# Arduino.net
KiCad netlist of a schematic drawn in Altium Designer
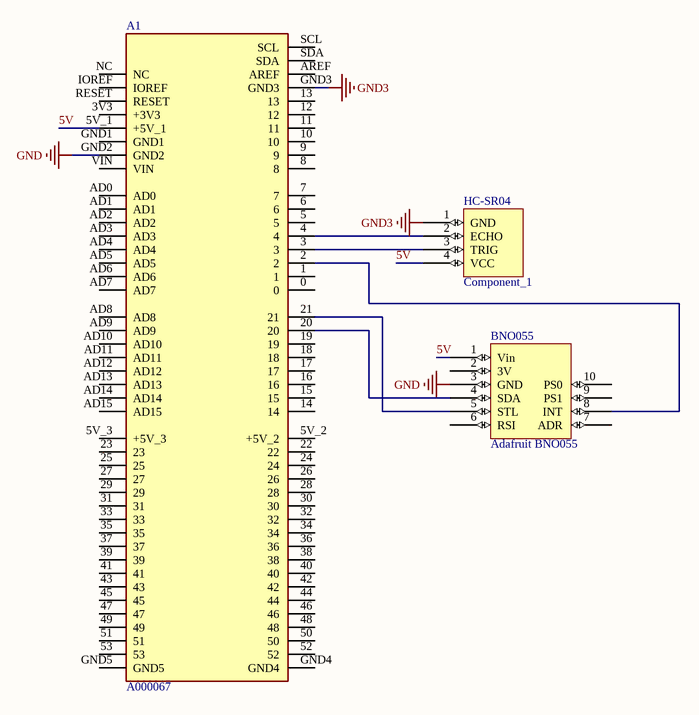
[diagram p0: Arduino.SchDoc]

(export (version "E")
  (design (tool "Eeschema 10.0.6"))
  (components
    (comp (ref "A1")
      (value "A000067")
      (footprint "ARDUINO_A000067")
      (description "8-bit board with 54 digital pins, 16 analog inputs, and 4 serial ports.")
      (fields (field (name "MF") "Arduino") (field (name "MP") "Arduino Mega 2560 Rev3"))
      (libsource (lib "A000067") (part "A000067"))
    )
    (comp (ref "BNO055")
      (value "Adafruit BNO055")
      (footprint "PCBComponent_1")
      (libsource (lib "Adafruit BNO055") (part "Component_1"))
    )
    (comp (ref "HC-SR04")
      (value "Component_1")
      (footprint "Ultrasonic Header:PCBComponent_1")
      (libsource (lib "Ultrasonic Header") (part "Component_1"))
    )
  )
  (nets
    (net (code "1") (name "/5V") (class "Default")
      (node (ref "A1") (pin "5V_1") (pinfunction "+5V_1_5V_1") (pintype "passive"))
      (node (ref "BNO055") (pin "1") (pinfunction "Vin_1") (pintype "bidirectional"))
      (node (ref "HC-SR04") (pin "4") (pinfunction "VCC_4") (pintype "bidirectional"))
    )
    (net (code "2") (name "GND") (class "Default")
      (node (ref "A1") (pin "GND2") (pinfunction "GND2_GND2") (pintype "passive"))
      (node (ref "BNO055") (pin "3") (pinfunction "GND_3") (pintype "bidirectional"))
    )
    (net (code "3") (name "GND3") (class "Default")
      (node (ref "A1") (pin "GND3") (pinfunction "GND3_GND3") (pintype "passive"))
      (node (ref "HC-SR04") (pin "1") (pinfunction "GND_1") (pintype "bidirectional"))
    )
    (net (code "4") (name "Net-(BNO055-INT)") (class "Default")
      (node (ref "A1") (pin "2") (pinfunction "2_2") (pintype "passive"))
      (node (ref "BNO055") (pin "8") (pinfunction "INT_8") (pintype "bidirectional"))
    )
    (net (code "5") (name "Net-(BNO055-SDA)") (class "Default")
      (node (ref "A1") (pin "20") (pinfunction "20_20") (pintype "passive"))
      (node (ref "BNO055") (pin "4") (pinfunction "SDA_4") (pintype "bidirectional"))
    )
    (net (code "6") (name "Net-(BNO055-STL)") (class "Default")
      (node (ref "A1") (pin "21") (pinfunction "21_21") (pintype "passive"))
      (node (ref "BNO055") (pin "5") (pinfunction "STL_5") (pintype "bidirectional"))
    )
    (net (code "7") (name "Net-(HC-SR04-ECHO)") (class "Default")
      (node (ref "A1") (pin "4") (pinfunction "4_4") (pintype "passive"))
      (node (ref "HC-SR04") (pin "2") (pinfunction "ECHO_2") (pintype "bidirectional"))
    )
    (net (code "8") (name "Net-(HC-SR04-TRIG)") (class "Default")
      (node (ref "A1") (pin "3") (pinfunction "3_3") (pintype "passive"))
      (node (ref "HC-SR04") (pin "3") (pinfunction "TRIG_3") (pintype "bidirectional"))
    )
    (net (code "9") (name "unconnected-(A1-+3V3-Pad3V3)") (class "Default")
      (node (ref "A1") (pin "3V3") (pinfunction "+3V3_3V3") (pintype "passive"))
    )
    (net (code "10") (name "unconnected-(A1-+5V_2-Pad5V_2)") (class "Default")
      (node (ref "A1") (pin "5V_2") (pinfunction "+5V_2_5V_2") (pintype "passive"))
    )
    (net (code "11") (name "unconnected-(A1-+5V_3-Pad5V_3)") (class "Default")
      (node (ref "A1") (pin "5V_3") (pinfunction "+5V_3_5V_3") (pintype "passive"))
    )
    (net (code "12") (name "unconnected-(A1-Pad0)") (class "Default")
      (node (ref "A1") (pin "0") (pinfunction "0_0") (pintype "passive"))
    )
    (net (code "13") (name "unconnected-(A1-Pad1)") (class "Default")
      (node (ref "A1") (pin "1") (pinfunction "1_1") (pintype "passive"))
    )
    (net (code "14") (name "unconnected-(A1-Pad5)") (class "Default")
      (node (ref "A1") (pin "5") (pinfunction "5_5") (pintype "passive"))
    )
    (net (code "15") (name "unconnected-(A1-Pad6)") (class "Default")
      (node (ref "A1") (pin "6") (pinfunction "6_6") (pintype "passive"))
    )
    (net (code "16") (name "unconnected-(A1-Pad7)") (class "Default")
      (node (ref "A1") (pin "7") (pinfunction "7_7") (pintype "passive"))
    )
    (net (code "17") (name "unconnected-(A1-Pad8)") (class "Default")
      (node (ref "A1") (pin "8") (pinfunction "8_8") (pintype "passive"))
    )
    (net (code "18") (name "unconnected-(A1-Pad9)") (class "Default")
      (node (ref "A1") (pin "9") (pinfunction "9_9") (pintype "passive"))
    )
    (net (code "19") (name "unconnected-(A1-Pad10)") (class "Default")
      (node (ref "A1") (pin "10") (pinfunction "10_10") (pintype "passive"))
    )
    (net (code "20") (name "unconnected-(A1-Pad11)") (class "Default")
      (node (ref "A1") (pin "11") (pinfunction "11_11") (pintype "passive"))
    )
    (net (code "21") (name "unconnected-(A1-Pad12)") (class "Default")
      (node (ref "A1") (pin "12") (pinfunction "12_12") (pintype "passive"))
    )
    (net (code "22") (name "unconnected-(A1-Pad13)") (class "Default")
      (node (ref "A1") (pin "13") (pinfunction "13_13") (pintype "passive"))
    )
    (net (code "23") (name "unconnected-(A1-Pad14)") (class "Default")
      (node (ref "A1") (pin "14") (pinfunction "14_14") (pintype "passive"))
    )
    (net (code "24") (name "unconnected-(A1-Pad15)") (class "Default")
      (node (ref "A1") (pin "15") (pinfunction "15_15") (pintype "passive"))
    )
    (net (code "25") (name "unconnected-(A1-Pad16)") (class "Default")
      (node (ref "A1") (pin "16") (pinfunction "16_16") (pintype "passive"))
    )
    (net (code "26") (name "unconnected-(A1-Pad17)") (class "Default")
      (node (ref "A1") (pin "17") (pinfunction "17_17") (pintype "passive"))
    )
    (net (code "27") (name "unconnected-(A1-Pad18)") (class "Default")
      (node (ref "A1") (pin "18") (pinfunction "18_18") (pintype "passive"))
    )
    (net (code "28") (name "unconnected-(A1-Pad19)") (class "Default")
      (node (ref "A1") (pin "19") (pinfunction "19_19") (pintype "passive"))
    )
    (net (code "29") (name "unconnected-(A1-Pad22)") (class "Default")
      (node (ref "A1") (pin "22") (pinfunction "22_22") (pintype "passive"))
    )
    (net (code "30") (name "unconnected-(A1-Pad23)") (class "Default")
      (node (ref "A1") (pin "23") (pinfunction "23_23") (pintype "passive"))
    )
    (net (code "31") (name "unconnected-(A1-Pad24)") (class "Default")
      (node (ref "A1") (pin "24") (pinfunction "24_24") (pintype "passive"))
    )
    (net (code "32") (name "unconnected-(A1-Pad25)") (class "Default")
      (node (ref "A1") (pin "25") (pinfunction "25_25") (pintype "passive"))
    )
    (net (code "33") (name "unconnected-(A1-Pad26)") (class "Default")
      (node (ref "A1") (pin "26") (pinfunction "26_26") (pintype "passive"))
    )
    (net (code "34") (name "unconnected-(A1-Pad27)") (class "Default")
      (node (ref "A1") (pin "27") (pinfunction "27_27") (pintype "passive"))
    )
    (net (code "35") (name "unconnected-(A1-Pad28)") (class "Default")
      (node (ref "A1") (pin "28") (pinfunction "28_28") (pintype "passive"))
    )
    (net (code "36") (name "unconnected-(A1-Pad29)") (class "Default")
      (node (ref "A1") (pin "29") (pinfunction "29_29") (pintype "passive"))
    )
    (net (code "37") (name "unconnected-(A1-Pad30)") (class "Default")
      (node (ref "A1") (pin "30") (pinfunction "30_30") (pintype "passive"))
    )
    (net (code "38") (name "unconnected-(A1-Pad31)") (class "Default")
      (node (ref "A1") (pin "31") (pinfunction "31_31") (pintype "passive"))
    )
    (net (code "39") (name "unconnected-(A1-Pad32)") (class "Default")
      (node (ref "A1") (pin "32") (pinfunction "32_32") (pintype "passive"))
    )
    (net (code "40") (name "unconnected-(A1-Pad33)") (class "Default")
      (node (ref "A1") (pin "33") (pinfunction "33_33") (pintype "passive"))
    )
    (net (code "41") (name "unconnected-(A1-Pad34)") (class "Default")
      (node (ref "A1") (pin "34") (pinfunction "34_34") (pintype "passive"))
    )
    (net (code "42") (name "unconnected-(A1-Pad35)") (class "Default")
      (node (ref "A1") (pin "35") (pinfunction "35_35") (pintype "passive"))
    )
    (net (code "43") (name "unconnected-(A1-Pad36)") (class "Default")
      (node (ref "A1") (pin "36") (pinfunction "36_36") (pintype "passive"))
    )
    (net (code "44") (name "unconnected-(A1-Pad37)") (class "Default")
      (node (ref "A1") (pin "37") (pinfunction "37_37") (pintype "passive"))
    )
    (net (code "45") (name "unconnected-(A1-Pad38)") (class "Default")
      (node (ref "A1") (pin "38") (pinfunction "38_38") (pintype "passive"))
    )
    (net (code "46") (name "unconnected-(A1-Pad39)") (class "Default")
      (node (ref "A1") (pin "39") (pinfunction "39_39") (pintype "passive"))
    )
    (net (code "47") (name "unconnected-(A1-Pad40)") (class "Default")
      (node (ref "A1") (pin "40") (pinfunction "40_40") (pintype "passive"))
    )
    (net (code "48") (name "unconnected-(A1-Pad41)") (class "Default")
      (node (ref "A1") (pin "41") (pinfunction "41_41") (pintype "passive"))
    )
    (net (code "49") (name "unconnected-(A1-Pad42)") (class "Default")
      (node (ref "A1") (pin "42") (pinfunction "42_42") (pintype "passive"))
    )
    (net (code "50") (name "unconnected-(A1-Pad43)") (class "Default")
      (node (ref "A1") (pin "43") (pinfunction "43_43") (pintype "passive"))
    )
    (net (code "51") (name "unconnected-(A1-Pad44)") (class "Default")
      (node (ref "A1") (pin "44") (pinfunction "44_44") (pintype "passive"))
    )
    (net (code "52") (name "unconnected-(A1-Pad45)") (class "Default")
      (node (ref "A1") (pin "45") (pinfunction "45_45") (pintype "passive"))
    )
    (net (code "53") (name "unconnected-(A1-Pad46)") (class "Default")
      (node (ref "A1") (pin "46") (pinfunction "46_46") (pintype "passive"))
    )
    (net (code "54") (name "unconnected-(A1-Pad47)") (class "Default")
      (node (ref "A1") (pin "47") (pinfunction "47_47") (pintype "passive"))
    )
    (net (code "55") (name "unconnected-(A1-Pad48)") (class "Default")
      (node (ref "A1") (pin "48") (pinfunction "48_48") (pintype "passive"))
    )
    (net (code "56") (name "unconnected-(A1-Pad49)") (class "Default")
      (node (ref "A1") (pin "49") (pinfunction "49_49") (pintype "passive"))
    )
    (net (code "57") (name "unconnected-(A1-Pad50)") (class "Default")
      (node (ref "A1") (pin "50") (pinfunction "50_50") (pintype "passive"))
    )
    (net (code "58") (name "unconnected-(A1-Pad51)") (class "Default")
      (node (ref "A1") (pin "51") (pinfunction "51_51") (pintype "passive"))
    )
    (net (code "59") (name "unconnected-(A1-Pad52)") (class "Default")
      (node (ref "A1") (pin "52") (pinfunction "52_52") (pintype "passive"))
    )
    (net (code "60") (name "unconnected-(A1-Pad53)") (class "Default")
      (node (ref "A1") (pin "53") (pinfunction "53_53") (pintype "passive"))
    )
    (net (code "61") (name "unconnected-(A1-PadAD0)") (class "Default")
      (node (ref "A1") (pin "AD0") (pinfunction "AD0_AD0") (pintype "passive"))
    )
    (net (code "62") (name "unconnected-(A1-PadAD1)") (class "Default")
      (node (ref "A1") (pin "AD1") (pinfunction "AD1_AD1") (pintype "passive"))
    )
    (net (code "63") (name "unconnected-(A1-PadAD2)") (class "Default")
      (node (ref "A1") (pin "AD2") (pinfunction "AD2_AD2") (pintype "passive"))
    )
    (net (code "64") (name "unconnected-(A1-PadAD3)") (class "Default")
      (node (ref "A1") (pin "AD3") (pinfunction "AD3_AD3") (pintype "passive"))
    )
    (net (code "65") (name "unconnected-(A1-PadAD4)") (class "Default")
      (node (ref "A1") (pin "AD4") (pinfunction "AD4_AD4") (pintype "passive"))
    )
    (net (code "66") (name "unconnected-(A1-PadAD5)") (class "Default")
      (node (ref "A1") (pin "AD5") (pinfunction "AD5_AD5") (pintype "passive"))
    )
    (net (code "67") (name "unconnected-(A1-PadAD6)") (class "Default")
      (node (ref "A1") (pin "AD6") (pinfunction "AD6_AD6") (pintype "passive"))
    )
    (net (code "68") (name "unconnected-(A1-PadAD7)") (class "Default")
      (node (ref "A1") (pin "AD7") (pinfunction "AD7_AD7") (pintype "passive"))
    )
    (net (code "69") (name "unconnected-(A1-PadAD8)") (class "Default")
      (node (ref "A1") (pin "AD8") (pinfunction "AD8_AD8") (pintype "passive"))
    )
    (net (code "70") (name "unconnected-(A1-PadAD9)") (class "Default")
      (node (ref "A1") (pin "AD9") (pinfunction "AD9_AD9") (pintype "passive"))
    )
    (net (code "71") (name "unconnected-(A1-PadAD10)") (class "Default")
      (node (ref "A1") (pin "AD10") (pinfunction "AD10_AD10") (pintype "passive"))
    )
    (net (code "72") (name "unconnected-(A1-PadAD11)") (class "Default")
      (node (ref "A1") (pin "AD11") (pinfunction "AD11_AD11") (pintype "passive"))
    )
    (net (code "73") (name "unconnected-(A1-PadAD12)") (class "Default")
      (node (ref "A1") (pin "AD12") (pinfunction "AD12_AD12") (pintype "passive"))
    )
    (net (code "74") (name "unconnected-(A1-PadAD13)") (class "Default")
      (node (ref "A1") (pin "AD13") (pinfunction "AD13_AD13") (pintype "passive"))
    )
    (net (code "75") (name "unconnected-(A1-PadAD14)") (class "Default")
      (node (ref "A1") (pin "AD14") (pinfunction "AD14_AD14") (pintype "passive"))
    )
    (net (code "76") (name "unconnected-(A1-PadAD15)") (class "Default")
      (node (ref "A1") (pin "AD15") (pinfunction "AD15_AD15") (pintype "passive"))
    )
    (net (code "77") (name "unconnected-(A1-PadAREF)") (class "Default")
      (node (ref "A1") (pin "AREF") (pinfunction "AREF_AREF") (pintype "passive"))
    )
    (net (code "78") (name "unconnected-(A1-PadGND1)") (class "Default")
      (node (ref "A1") (pin "GND1") (pinfunction "GND1_GND1") (pintype "passive"))
    )
    (net (code "79") (name "unconnected-(A1-PadGND4)") (class "Default")
      (node (ref "A1") (pin "GND4") (pinfunction "GND4_GND4") (pintype "passive"))
    )
    (net (code "80") (name "unconnected-(A1-PadGND5)") (class "Default")
      (node (ref "A1") (pin "GND5") (pinfunction "GND5_GND5") (pintype "passive"))
    )
    (net (code "81") (name "unconnected-(A1-PadIOREF)") (class "Default")
      (node (ref "A1") (pin "IOREF") (pinfunction "IOREF_IOREF") (pintype "passive"))
    )
    (net (code "82") (name "unconnected-(A1-PadNC)") (class "Default")
      (node (ref "A1") (pin "NC") (pinfunction "NC_NC") (pintype "passive"))
    )
    (net (code "83") (name "unconnected-(A1-PadRESET)") (class "Default")
      (node (ref "A1") (pin "RESET") (pinfunction "RESET_RESET") (pintype "passive"))
    )
    (net (code "84") (name "unconnected-(A1-PadSCL)") (class "Default")
      (node (ref "A1") (pin "SCL") (pinfunction "SCL_SCL") (pintype "passive"))
    )
    (net (code "85") (name "unconnected-(A1-PadSDA)") (class "Default")
      (node (ref "A1") (pin "SDA") (pinfunction "SDA_SDA") (pintype "passive"))
    )
    (net (code "86") (name "unconnected-(A1-PadVIN)") (class "Default")
      (node (ref "A1") (pin "VIN") (pinfunction "VIN_VIN") (pintype "passive"))
    )
    (net (code "87") (name "unconnected-(BNO055-3V-Pad2)") (class "Default")
      (node (ref "BNO055") (pin "2") (pinfunction "3V_2") (pintype "bidirectional"))
    )
    (net (code "88") (name "unconnected-(BNO055-ADR-Pad7)") (class "Default")
      (node (ref "BNO055") (pin "7") (pinfunction "ADR_7") (pintype "bidirectional"))
    )
    (net (code "89") (name "unconnected-(BNO055-PS0-Pad10)") (class "Default")
      (node (ref "BNO055") (pin "10") (pinfunction "PS0_10") (pintype "bidirectional"))
    )
    (net (code "90") (name "unconnected-(BNO055-PS1-Pad9)") (class "Default")
      (node (ref "BNO055") (pin "9") (pinfunction "PS1_9") (pintype "bidirectional"))
    )
    (net (code "91") (name "unconnected-(BNO055-RSI-Pad6)") (class "Default")
      (node (ref "BNO055") (pin "6") (pinfunction "RSI_6") (pintype "bidirectional"))
    )
  )
)
